# circuito_tesi.net
KiCad netlist of a schematic drawn in EAGLE
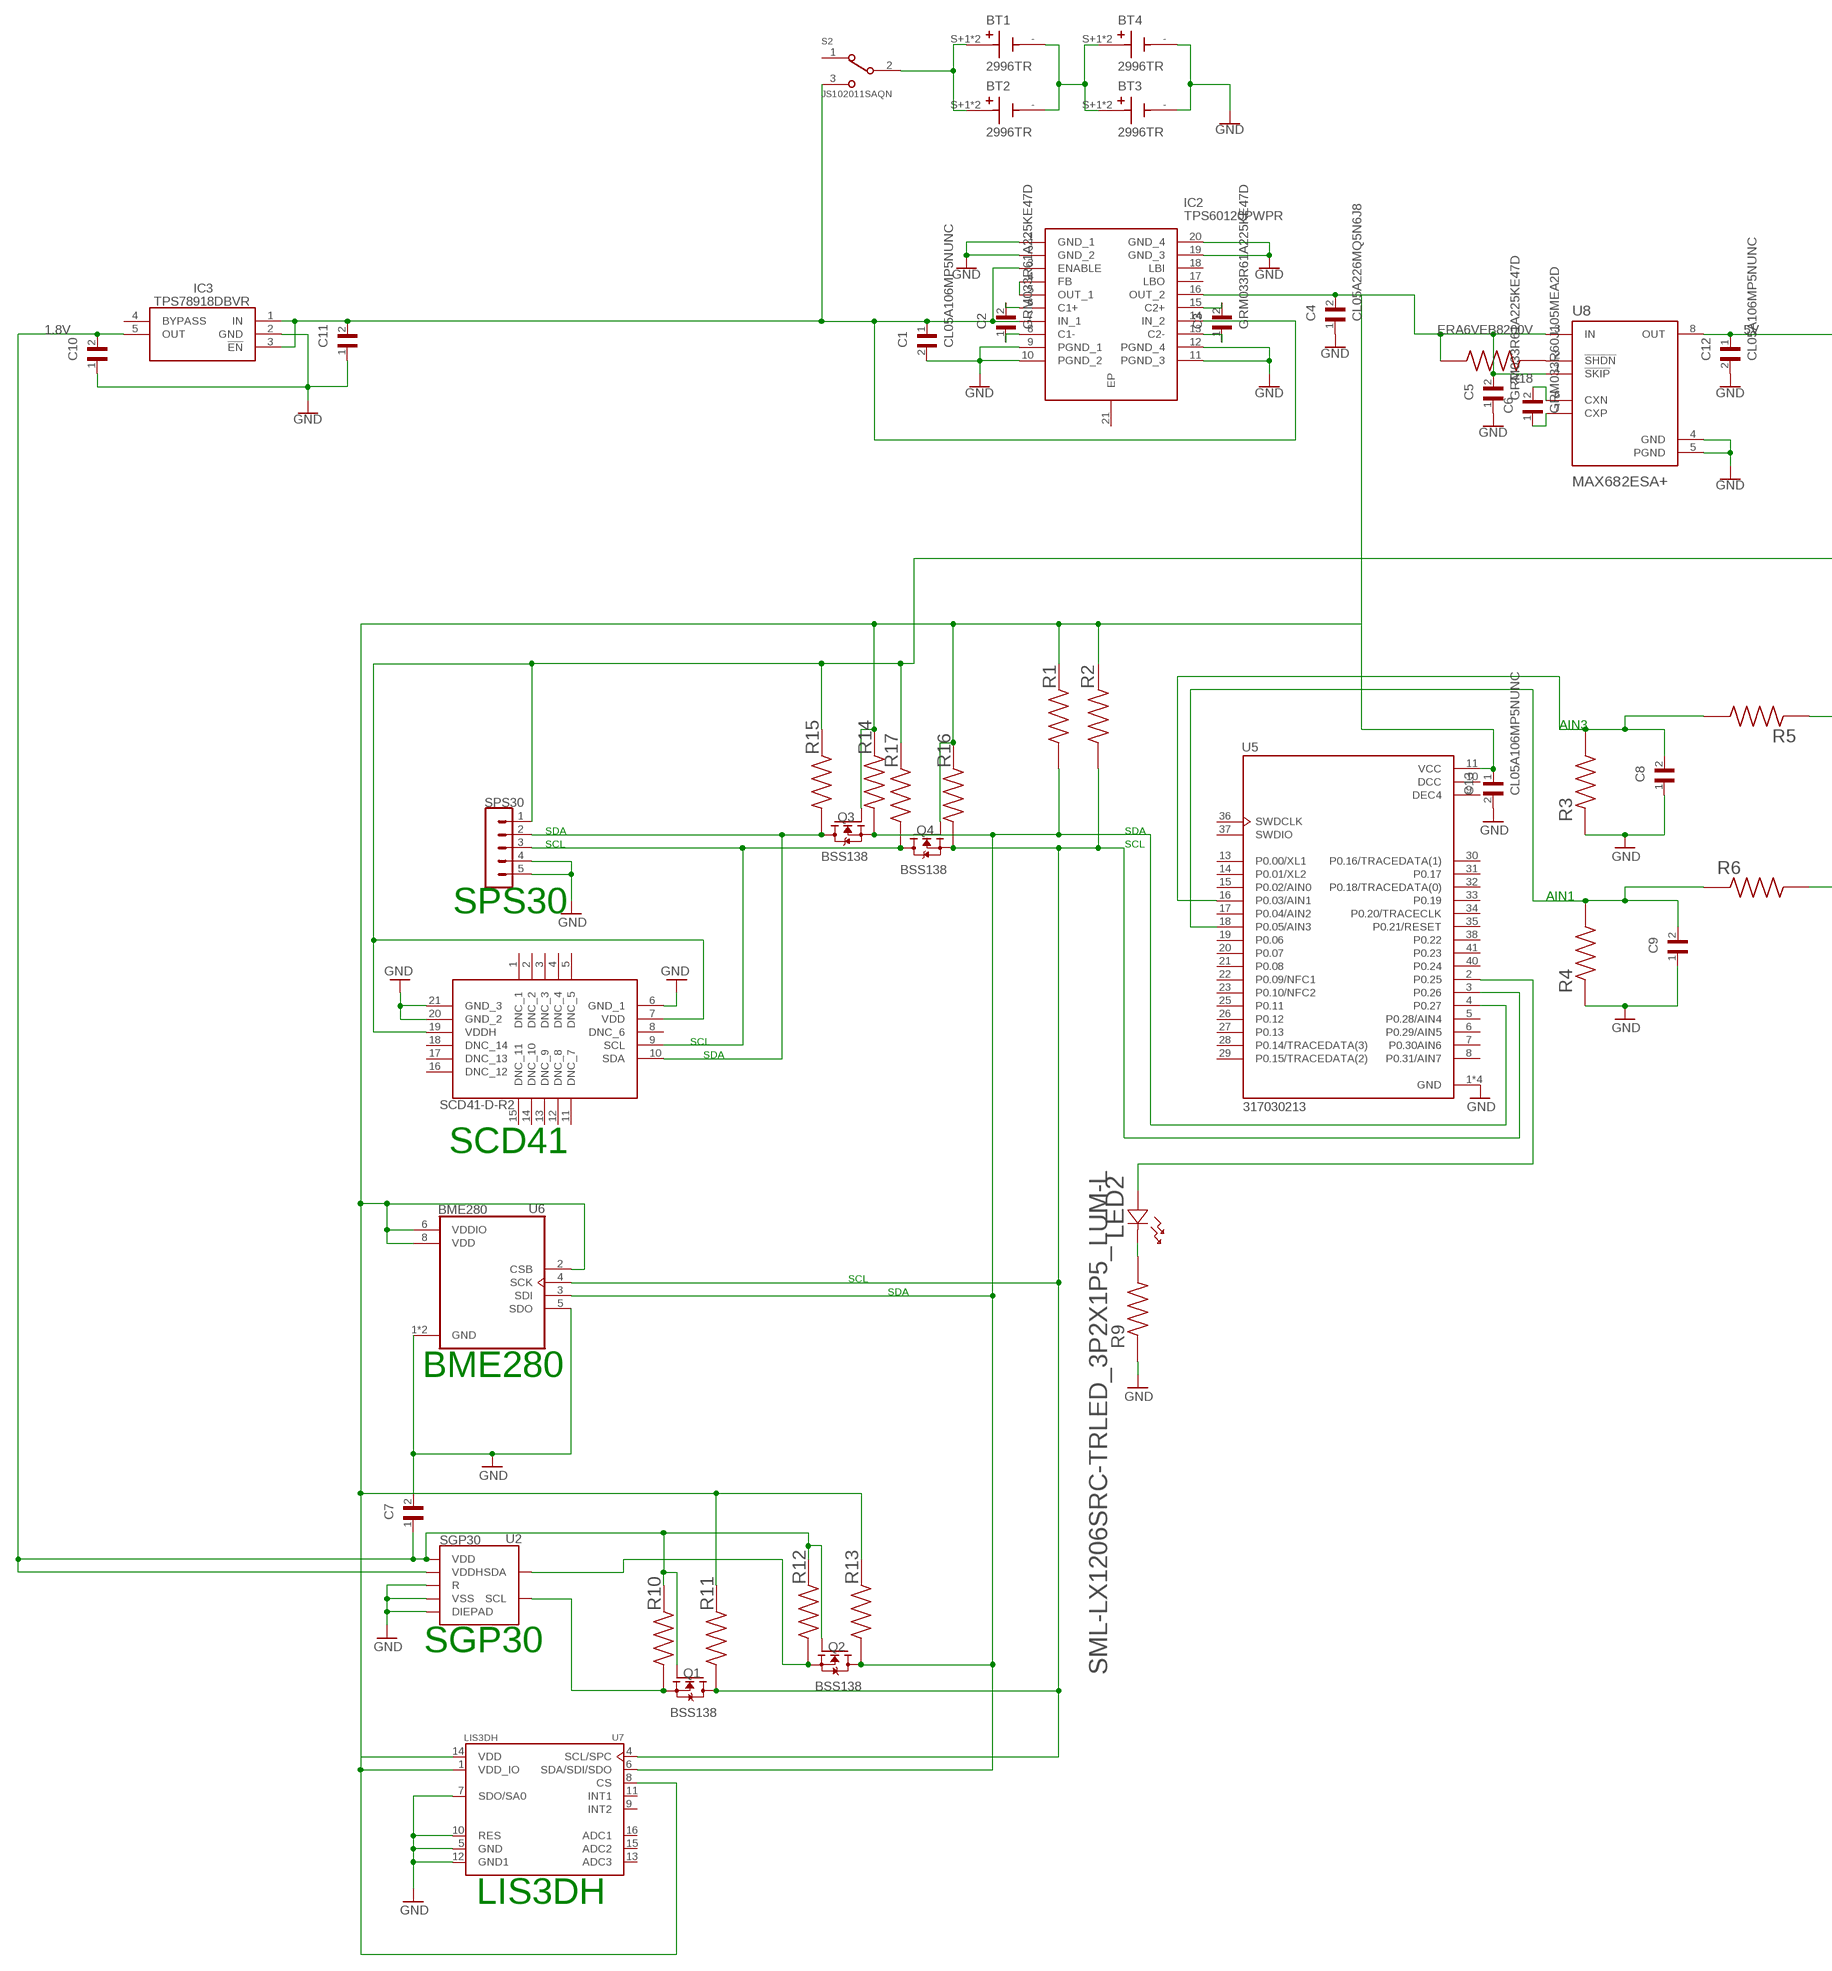
[diagram p0: schematic, sheet 1, part 1 of 2]
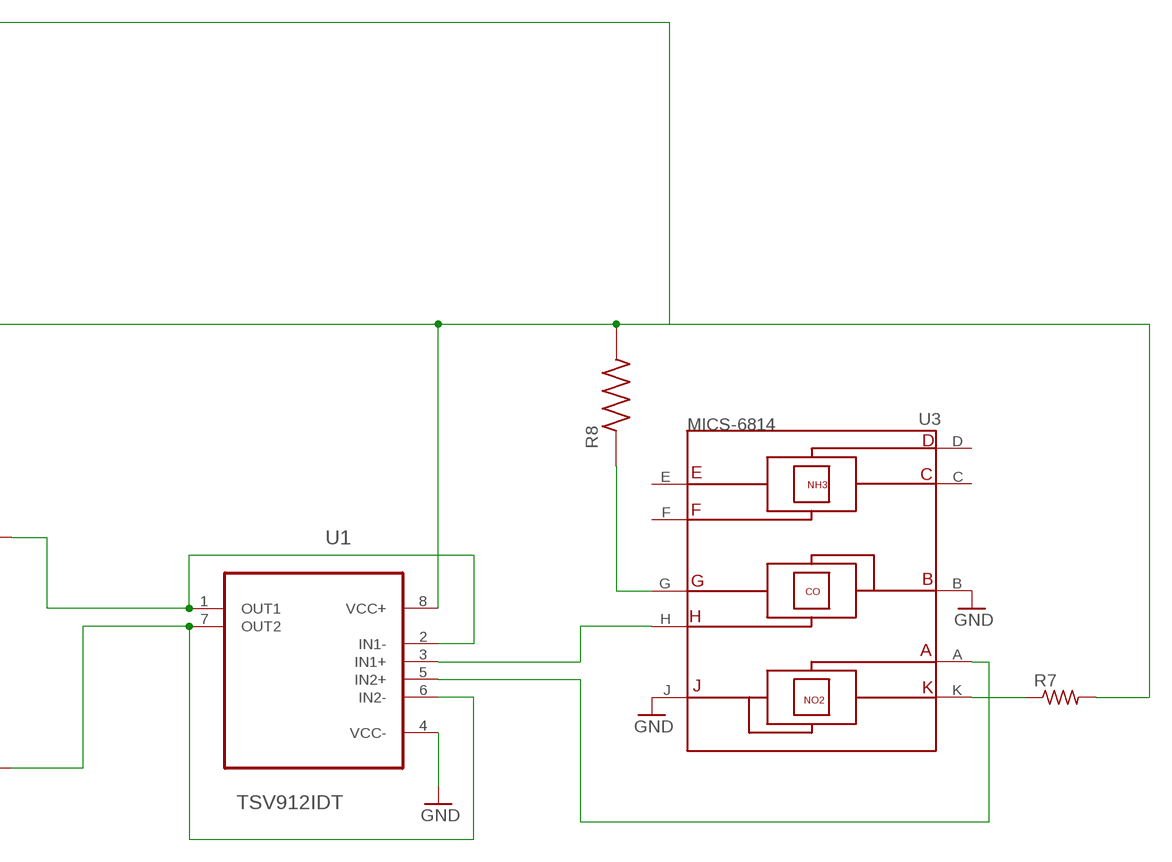
[diagram p1: schematic, sheet 1, part 2 of 2]

(export (version "E")
  (design (tool "Eeschema 10.0.6"))
  (components
    (comp (ref "BT1")
      (value "2996TR")
      (footprint "eagle-import:BAT_2996TR")
      (fields (field (name "DIGI-KEY_PART_NUMBER") "36-2996TR-ND") (field (name "MF") "Keystone Electronics"))
      (libsource (lib "eagle-import") (part "2996TR"))
    )
    (comp (ref "BT2")
      (value "2996TR")
      (footprint "eagle-import:BAT_2996TR")
      (fields (field (name "DIGI-KEY_PART_NUMBER") "36-2996TR-ND") (field (name "MF") "Keystone Electronics"))
      (libsource (lib "eagle-import") (part "2996TR"))
    )
    (comp (ref "BT3")
      (value "2996TR")
      (footprint "eagle-import:BAT_2996TR")
      (fields (field (name "DIGI-KEY_PART_NUMBER") "36-2996TR-ND") (field (name "MF") "Keystone Electronics"))
      (libsource (lib "eagle-import") (part "2996TR"))
    )
    (comp (ref "BT4")
      (value "2996TR")
      (footprint "eagle-import:BAT_2996TR")
      (fields (field (name "DIGI-KEY_PART_NUMBER") "36-2996TR-ND") (field (name "MF") "Keystone Electronics"))
      (libsource (lib "eagle-import") (part "2996TR"))
    )
    (comp (ref "C1")
      (value "CL05A106MP5NUNC")
      (footprint "eagle-import:CAPC1005X55N")
      (fields (field (name "DIGI-KEY_PART_NUMBER") "1276-1450-2-ND") (field (name "MF") "Samsung"))
      (libsource (lib "eagle-import") (part "CL05A106MP5NUNC"))
    )
    (comp (ref "C2")
      (value "GRM033R61A225KE47D")
      (footprint "eagle-import:CAPC0603X39N")
      (fields (field (name "DIGI-KEY_PART_NUMBER") "490-13227-2-ND") (field (name "MF") "Murata Electronics"))
      (libsource (lib "eagle-import") (part "GRM033R61A225KE47D"))
    )
    (comp (ref "C3")
      (value "GRM033R61A225KE47D")
      (footprint "eagle-import:CAPC0603X39N")
      (fields (field (name "DIGI-KEY_PART_NUMBER") "490-13227-2-ND") (field (name "MF") "Murata Electronics"))
      (libsource (lib "eagle-import") (part "GRM033R61A225KE47D"))
    )
    (comp (ref "C4")
      (value "CL05A226MQ5N6J8")
      (footprint "eagle-import:CAPC1005X55N")
      (fields
        (field (name "DIGI-KEY_PART_NUMBER") "1276-7090-2-ND")
        (field (name "MF") "Samsung Electro-Mechanics")
      )
      (libsource (lib "eagle-import") (part "CL05A226MQ5N6J8"))
    )
    (comp (ref "C5")
      (value "GRM033R61A225KE47D")
      (footprint "eagle-import:CAPC0603X39N")
      (fields (field (name "DIGI-KEY_PART_NUMBER") "490-13227-2-ND") (field (name "MF") "Murata Electronics"))
      (libsource (lib "eagle-import") (part "GRM033R61A225KE47D"))
    )
    (comp (ref "C6")
      (value "GRM033R60J105MEA2D")
      (footprint "eagle-import:CAPC0603X35N")
      (fields (field (name "DIGI-KEY_PART_NUMBER") "490-7229-2-ND") (field (name "MF") "Murata"))
      (libsource (lib "eagle-import") (part "GRM033R60J105MEA2D"))
    )
    (comp (ref "C7")
      (value "GRM033C80J104KE15D")
      (footprint "eagle-import:CAPC0603X33N")
      (fields (field (name "DIGI-KEY_PART_NUMBER") "490-10390-2-ND") (field (name "MF") "Murata Electronics"))
      (libsource (lib "eagle-import") (part "GRM033C80J104KE15D"))
    )
    (comp (ref "C8")
      (value "GRM033R60J103KA01D")
      (footprint "eagle-import:CAPC0603X33N")
      (fields (field (name "DIGI-KEY_PART_NUMBER") "490-5403-2-ND") (field (name "MF") "Murata"))
      (libsource (lib "eagle-import") (part "GRM033R60J103KA01D"))
    )
    (comp (ref "C9")
      (value "GRM033R60J103KA01D")
      (footprint "eagle-import:CAPC0603X33N")
      (fields (field (name "DIGI-KEY_PART_NUMBER") "490-5403-2-ND") (field (name "MF") "Murata"))
      (libsource (lib "eagle-import") (part "GRM033R60J103KA01D"))
    )
    (comp (ref "C10")
      (value "GRM033R60J105MEA2D")
      (footprint "eagle-import:CAPC0603X35N")
      (fields (field (name "DIGI-KEY_PART_NUMBER") "490-7229-2-ND") (field (name "MF") "Murata"))
      (libsource (lib "eagle-import") (part "GRM033R60J105MEA2D"))
    )
    (comp (ref "C11")
      (value "GRM033R60J105MEA2D")
      (footprint "eagle-import:CAPC0603X35N")
      (fields (field (name "DIGI-KEY_PART_NUMBER") "490-7229-2-ND") (field (name "MF") "Murata"))
      (libsource (lib "eagle-import") (part "GRM033R60J105MEA2D"))
    )
    (comp (ref "C12")
      (value "CL05A106MP5NUNC")
      (footprint "eagle-import:CAPC1005X55N")
      (fields (field (name "DIGI-KEY_PART_NUMBER") "1276-1450-2-ND") (field (name "MF") "Samsung"))
      (libsource (lib "eagle-import") (part "CL05A106MP5NUNC"))
    )
    (comp (ref "C13")
      (value "CL05A106MP5NUNC")
      (footprint "eagle-import:CAPC1005X55N")
      (fields (field (name "DIGI-KEY_PART_NUMBER") "1276-1450-2-ND") (field (name "MF") "Samsung"))
      (libsource (lib "eagle-import") (part "CL05A106MP5NUNC"))
    )
    (comp (ref "IC1")
      (value "SCD41-D-R2")
      (footprint "eagle-import:SCD41DR2")
      (fields (field (name "MOUSER_PART_NUMBER") "403-SCD41-D-R2"))
      (libsource (lib "eagle-import") (part "SCD41-D-R2"))
    )
    (comp (ref "IC2")
      (value "TPS60120PWPR")
      (footprint "eagle-import:SOP65P640X120-21N")
      (fields (field (name "MOUSER_PART_NUMBER") "595-TPS60120PWPR"))
      (libsource (lib "eagle-import") (part "TPS60120PWPR"))
    )
    (comp (ref "IC3")
      (value "TPS78918DBVR")
      (footprint "eagle-import:SOT95P280X145-5N")
      (fields (field (name "MOUSER_PART_NUMBER") "595-TPS78918DBVR"))
      (libsource (lib "eagle-import") (part "TPS78918DBVR"))
    )
    (comp (ref "LED2")
      (value "SML-LX1206SRC-TRLED_3P2X1P5_LUM-L")
      (footprint "eagle-import:LED_3P2X1P5_LUM-L")
      (fields
        (field (name "MANUFACTURER_PART_NUMBER") "SML-LX1206SRC-TR")
        (field (name "COPYRIGHT") "Copyright (C) 2022 Ultra Librarian. All rights reserved.")
      )
      (libsource (lib "eagle-import") (part "SML-LX1206SRC-TRLED_3P2X1P5_LUM-L"))
    )
    (comp (ref "Q1")
      (value "BSS138")
      (footprint "eagle-import:SOT95P240X111-3N")
      (fields (field (name "DIGI-KEY_PART_NUMBER") "BSS138TR-ND") (field (name "MF") "ON Semiconductor"))
      (libsource (lib "eagle-import") (part "BSS138"))
    )
    (comp (ref "Q2")
      (value "BSS138")
      (footprint "eagle-import:SOT95P240X111-3N")
      (fields (field (name "DIGI-KEY_PART_NUMBER") "BSS138TR-ND") (field (name "MF") "ON Semiconductor"))
      (libsource (lib "eagle-import") (part "BSS138"))
    )
    (comp (ref "Q3")
      (value "BSS138")
      (footprint "eagle-import:SOT95P240X111-3N")
      (fields (field (name "DIGI-KEY_PART_NUMBER") "BSS138TR-ND") (field (name "MF") "ON Semiconductor"))
      (libsource (lib "eagle-import") (part "BSS138"))
    )
    (comp (ref "Q4")
      (value "BSS138")
      (footprint "eagle-import:SOT95P240X111-3N")
      (fields (field (name "DIGI-KEY_PART_NUMBER") "BSS138TR-ND") (field (name "MF") "ON Semiconductor"))
      (libsource (lib "eagle-import") (part "BSS138"))
    )
    (comp (ref "R1")
      (value "RNCP0805FTD10K0")
      (footprint "eagle-import:RESC2012X60N")
      (fields
        (field (name "DIGI-KEY_PART_NUMBER") "RNCP0805FTD10K0TR-ND")
        (field (name "MF") "Stackpole Electronics Inc")
      )
      (libsource (lib "eagle-import") (part "RNCP0805FTD10K0"))
    )
    (comp (ref "R2")
      (value "RNCP0805FTD10K0")
      (footprint "eagle-import:RESC2012X60N")
      (fields
        (field (name "DIGI-KEY_PART_NUMBER") "RNCP0805FTD10K0TR-ND")
        (field (name "MF") "Stackpole Electronics Inc")
      )
      (libsource (lib "eagle-import") (part "RNCP0805FTD10K0"))
    )
    (comp (ref "R3")
      (value "RMCF0603FT10M0")
      (footprint "eagle-import:RESC1508X55N")
      (fields
        (field (name "DIGI-KEY_PART_NUMBER") "RMCF0603FT10M0TR-ND")
        (field (name "MF") "Stackpole Electronics Inc")
      )
      (libsource (lib "eagle-import") (part "RMCF0603FT10M0"))
    )
    (comp (ref "R4")
      (value "RMCF0603FT10M0")
      (footprint "eagle-import:RESC1508X55N")
      (fields
        (field (name "DIGI-KEY_PART_NUMBER") "RMCF0603FT10M0TR-ND")
        (field (name "MF") "Stackpole Electronics Inc")
      )
      (libsource (lib "eagle-import") (part "RMCF0603FT10M0"))
    )
    (comp (ref "R5")
      (value "RMCF0603FT5M10")
      (footprint "eagle-import:RESC1508X55N")
      (fields
        (field (name "DIGI-KEY_PART_NUMBER") "RMCF0603FT5M10TR-ND")
        (field (name "MF") "Stackpole Electronics Inc")
      )
      (libsource (lib "eagle-import") (part "RMCF0603FT5M10"))
    )
    (comp (ref "R6")
      (value "RMCF0603FT5M10")
      (footprint "eagle-import:RESC1508X55N")
      (fields
        (field (name "DIGI-KEY_PART_NUMBER") "RMCF0603FT5M10TR-ND")
        (field (name "MF") "Stackpole Electronics Inc")
      )
      (libsource (lib "eagle-import") (part "RMCF0603FT5M10"))
    )
    (comp (ref "R7")
      (value "RP73PF2A130RBTDF")
      (footprint "eagle-import:RESC2012X65N")
      (fields (field (name "MF") "TE Connectivity"))
      (libsource (lib "eagle-import") (part "RP73PF2A130RBTDF"))
    )
    (comp (ref "R8")
      (value "ERA6VEB8200V")
      (footprint "eagle-import:RES_ERA6VEB8200V")
      (fields (field (name "DIGI-KEY_PART_NUMBER") "10-ERA-6VEB8200VTR-ND") (field (name "MF") "Panasonic"))
      (libsource (lib "eagle-import") (part "ERA6VEB8200V"))
    )
    (comp (ref "R9")
      (value "RNCF0603DTE820R")
      (footprint "eagle-import:RESC1508X55N")
      (fields
        (field (name "DIGI-KEY_PART_NUMBER") "RNCF0603DTE820RTR-ND")
        (field (name "MF") "Stackpole Electronics Inc")
      )
      (libsource (lib "eagle-import") (part "RNCF0603DTE820R"))
    )
    (comp (ref "R10")
      (value "RNCP0805FTD10K0")
      (footprint "eagle-import:RESC2012X60N")
      (fields
        (field (name "DIGI-KEY_PART_NUMBER") "RNCP0805FTD10K0TR-ND")
        (field (name "MF") "Stackpole Electronics Inc")
      )
      (libsource (lib "eagle-import") (part "RNCP0805FTD10K0"))
    )
    (comp (ref "R11")
      (value "RNCP0805FTD10K0")
      (footprint "eagle-import:RESC2012X60N")
      (fields
        (field (name "DIGI-KEY_PART_NUMBER") "RNCP0805FTD10K0TR-ND")
        (field (name "MF") "Stackpole Electronics Inc")
      )
      (libsource (lib "eagle-import") (part "RNCP0805FTD10K0"))
    )
    (comp (ref "R12")
      (value "RNCP0805FTD10K0")
      (footprint "eagle-import:RESC2012X60N")
      (fields
        (field (name "DIGI-KEY_PART_NUMBER") "RNCP0805FTD10K0TR-ND")
        (field (name "MF") "Stackpole Electronics Inc")
      )
      (libsource (lib "eagle-import") (part "RNCP0805FTD10K0"))
    )
    (comp (ref "R13")
      (value "RNCP0805FTD10K0")
      (footprint "eagle-import:RESC2012X60N")
      (fields
        (field (name "DIGI-KEY_PART_NUMBER") "RNCP0805FTD10K0TR-ND")
        (field (name "MF") "Stackpole Electronics Inc")
      )
      (libsource (lib "eagle-import") (part "RNCP0805FTD10K0"))
    )
    (comp (ref "R14")
      (value "RNCP0805FTD10K0")
      (footprint "eagle-import:RESC2012X60N")
      (fields
        (field (name "DIGI-KEY_PART_NUMBER") "RNCP0805FTD10K0TR-ND")
        (field (name "MF") "Stackpole Electronics Inc")
      )
      (libsource (lib "eagle-import") (part "RNCP0805FTD10K0"))
    )
    (comp (ref "R15")
      (value "RNCP0805FTD10K0")
      (footprint "eagle-import:RESC2012X60N")
      (fields
        (field (name "DIGI-KEY_PART_NUMBER") "RNCP0805FTD10K0TR-ND")
        (field (name "MF") "Stackpole Electronics Inc")
      )
      (libsource (lib "eagle-import") (part "RNCP0805FTD10K0"))
    )
    (comp (ref "R16")
      (value "RNCP0805FTD10K0")
      (footprint "eagle-import:RESC2012X60N")
      (fields
        (field (name "DIGI-KEY_PART_NUMBER") "RNCP0805FTD10K0TR-ND")
        (field (name "MF") "Stackpole Electronics Inc")
      )
      (libsource (lib "eagle-import") (part "RNCP0805FTD10K0"))
    )
    (comp (ref "R17")
      (value "RNCP0805FTD10K0")
      (footprint "eagle-import:RESC2012X60N")
      (fields
        (field (name "DIGI-KEY_PART_NUMBER") "RNCP0805FTD10K0TR-ND")
        (field (name "MF") "Stackpole Electronics Inc")
      )
      (libsource (lib "eagle-import") (part "RNCP0805FTD10K0"))
    )
    (comp (ref "R18")
      (value "ERA6VEB8200V")
      (footprint "eagle-import:RES_ERA6VEB8200V")
      (fields (field (name "DIGI-KEY_PART_NUMBER") "10-ERA-6VEB8200VTR-ND") (field (name "MF") "Panasonic"))
      (libsource (lib "eagle-import") (part "ERA6VEB8200V"))
    )
    (comp (ref "S2")
      (value "JS102011SAQN")
      (footprint "eagle-import:SW_JS102011SAQN")
      (fields (field (name "DIGI-KEY_PART_NUMBER") "401-1999-2-ND") (field (name "MF") "C&K"))
      (libsource (lib "eagle-import") (part "JS102011SAQN"))
    )
    (comp (ref "SPS30")
      (value "MA05-1")
      (footprint "eagle-import:MA05-1")
      (libsource (lib "eagle-import") (part "MA05-1"))
    )
    (comp (ref "U1")
      (value "TSV912IDT")
      (footprint "eagle-import:SOIC127P600X175-8N")
      (fields (field (name "MF") "STMicroelectronics"))
      (libsource (lib "eagle-import") (part "TSV912IDT"))
    )
    (comp (ref "U2")
      (value "SGP30")
      (footprint "eagle-import:SGP30")
      (fields (field (name "MF") "Sensirion AG"))
      (libsource (lib "eagle-import") (part "SGP30"))
    )
    (comp (ref "U3")
      (value "MICS-6814")
      (footprint "eagle-import:SENSOR_MICS-6814")
      (fields (field (name "MF") "MikroElektronika"))
      (libsource (lib "eagle-import") (part "MICS-6814"))
    )
    (comp (ref "U5")
      (value "317030213")
      (footprint "eagle-import:XCVR_317030213")
      (fields (field (name "DIGI-KEY_PART_NUMBER") "1597-1434-ND") (field (name "MF") "Seeed Technology"))
      (libsource (lib "eagle-import") (part "317030213"))
    )
    (comp (ref "U6")
      (value "BME280")
      (footprint "eagle-import:PSON65P250X250X100-8N")
      (fields (field (name "MF") "Bosch"))
      (libsource (lib "eagle-import") (part "BME280"))
    )
    (comp (ref "U7")
      (value "LIS3DH")
      (footprint "eagle-import:PQFN50P300X300X100-16N")
      (fields (field (name "DIGI-KEY_PART_NUMBER") "497-10610-ND") (field (name "MF") "STMicroelectronics"))
      (libsource (lib "eagle-import") (part "LIS3DH"))
    )
    (comp (ref "U8")
      (value "MAX682ESA+")
      (footprint "eagle-import:SOIC127P600X175-8N")
      (fields (field (name "DIGI-KEY_PART_NUMBER") "MAX682ESA+-ND") (field (name "MF") "Maxim Integrated"))
      (libsource (lib "eagle-import") (part "MAX682ESA+"))
    )
  )
  (nets
    (net (code "1") (name "/1.8V") (class "Default")
      (node (ref "C10") (pin "2") (pinfunction "2_2") (pintype "passive"))
      (node (ref "C7") (pin "1") (pinfunction "1_1") (pintype "passive"))
      (node (ref "IC3") (pin "5") (pinfunction "OUT_5") (pintype "bidirectional"))
      (node (ref "Q1") (pin "1") (pinfunction "G_1") (pintype "passive"))
      (node (ref "Q2") (pin "1") (pinfunction "G_1") (pintype "passive"))
      (node (ref "R10") (pin "2") (pinfunction "2_2") (pintype "passive"))
      (node (ref "R12") (pin "2") (pinfunction "2_2") (pintype "passive"))
      (node (ref "U2") (pin "1") (pinfunction "VDD_1") (pintype "bidirectional"))
      (node (ref "U2") (pin "5") (pinfunction "VDDH_5") (pintype "bidirectional"))
    )
    (net (code "2") (name "/5V") (class "Default")
      (node (ref "C12") (pin "1") (pinfunction "1_1") (pintype "passive"))
      (node (ref "IC1") (pin "19") (pinfunction "VDDH_19") (pintype "bidirectional"))
      (node (ref "IC1") (pin "7") (pinfunction "VDD_7") (pintype "bidirectional"))
      (node (ref "R15") (pin "2") (pinfunction "2_2") (pintype "passive"))
      (node (ref "R17") (pin "2") (pinfunction "2_2") (pintype "passive"))
      (node (ref "R7") (pin "2") (pinfunction "2_2") (pintype "passive"))
      (node (ref "R8") (pin "2") (pinfunction "2_2") (pintype "passive"))
      (node (ref "SPS30") (pin "1") (pinfunction "1_1") (pintype "passive"))
      (node (ref "U1") (pin "8") (pinfunction "VCC+_8") (pintype "power_in"))
      (node (ref "U8") (pin "8") (pinfunction "OUT_8") (pintype "output"))
    )
    (net (code "3") (name "/DCC") (class "Default")
      (node (ref "U5") (pin "10") (pinfunction "DCC_10") (pintype "power_in"))
    )
    (net (code "4") (name "/DEC4") (class "Default")
      (node (ref "U5") (pin "9") (pinfunction "DEC4_9") (pintype "power_in"))
    )
    (net (code "5") (name "GND") (class "Default")
      (node (ref "BT3") (pin "-") (pinfunction "-_-") (pintype "passive"))
      (node (ref "BT4") (pin "-") (pinfunction "-_-") (pintype "passive"))
      (node (ref "C1") (pin "2") (pinfunction "2_2") (pintype "passive"))
      (node (ref "C10") (pin "1") (pinfunction "1_1") (pintype "passive"))
      (node (ref "C11") (pin "1") (pinfunction "1_1") (pintype "passive"))
      (node (ref "C12") (pin "2") (pinfunction "2_2") (pintype "passive"))
      (node (ref "C13") (pin "2") (pinfunction "2_2") (pintype "passive"))
      (node (ref "C4") (pin "1") (pinfunction "1_1") (pintype "passive"))
      (node (ref "C5") (pin "1") (pinfunction "1_1") (pintype "passive"))
      (node (ref "C7") (pin "2") (pinfunction "2_2") (pintype "passive"))
      (node (ref "C8") (pin "1") (pinfunction "1_1") (pintype "passive"))
      (node (ref "C9") (pin "1") (pinfunction "1_1") (pintype "passive"))
      (node (ref "IC1") (pin "20") (pinfunction "GND_2_20") (pintype "bidirectional"))
      (node (ref "IC1") (pin "21") (pinfunction "GND_3_21") (pintype "bidirectional"))
      (node (ref "IC1") (pin "6") (pinfunction "GND_1_6") (pintype "bidirectional"))
      (node (ref "IC2") (pin "1") (pinfunction "GND_1_1") (pintype "bidirectional"))
      (node (ref "IC2") (pin "10") (pinfunction "PGND_2_10") (pintype "bidirectional"))
      (node (ref "IC2") (pin "11") (pinfunction "PGND_3_11") (pintype "bidirectional"))
      (node (ref "IC2") (pin "12") (pinfunction "PGND_4_12") (pintype "bidirectional"))
      (node (ref "IC2") (pin "19") (pinfunction "GND_3_19") (pintype "bidirectional"))
      (node (ref "IC2") (pin "2") (pinfunction "GND_2_2") (pintype "bidirectional"))
      (node (ref "IC2") (pin "20") (pinfunction "GND_4_20") (pintype "bidirectional"))
      (node (ref "IC2") (pin "9") (pinfunction "PGND_1_9") (pintype "bidirectional"))
      (node (ref "IC3") (pin "2") (pinfunction "GND_2") (pintype "bidirectional"))
      (node (ref "R3") (pin "1") (pinfunction "1_1") (pintype "passive"))
      (node (ref "R4") (pin "1") (pinfunction "1_1") (pintype "passive"))
      (node (ref "R9") (pin "1") (pinfunction "1_1") (pintype "passive"))
      (node (ref "SPS30") (pin "4") (pinfunction "4_4") (pintype "passive"))
      (node (ref "SPS30") (pin "5") (pinfunction "5_5") (pintype "passive"))
      (node (ref "U1") (pin "4") (pinfunction "VCC-_4") (pintype "power_in"))
      (node (ref "U2") (pin "2") (pinfunction "VSS_2") (pintype "bidirectional"))
      (node (ref "U2") (pin "4") (pinfunction "R_4") (pintype "bidirectional"))
      (node (ref "U2") (pin "DIEPAD") (pinfunction "DIEPAD_DIEPAD") (pintype "bidirectional"))
      (node (ref "U3") (pin "B") (pinfunction "RH1/RS1_RED_B") (pintype "passive"))
      (node (ref "U3") (pin "J") (pinfunction "RH1/RS1_OX_J") (pintype "passive"))
      (node (ref "U5") (pin "1") (pinfunction "GND_1") (pintype "power_in"))
      (node (ref "U5") (pin "12") (pinfunction "GND_12") (pintype "power_in"))
      (node (ref "U5") (pin "24") (pinfunction "GND_24") (pintype "power_in"))
      (node (ref "U5") (pin "39") (pinfunction "GND_39") (pintype "power_in"))
      (node (ref "U6") (pin "1") (pinfunction "GND_1") (pintype "power_in"))
      (node (ref "U6") (pin "5") (pinfunction "SDO_5") (pintype "bidirectional"))
      (node (ref "U6") (pin "7") (pinfunction "GND_7") (pintype "power_in"))
      (node (ref "U7") (pin "10") (pinfunction "RES_10") (pintype "power_in"))
      (node (ref "U7") (pin "12") (pinfunction "GND1_12") (pintype "power_in"))
      (node (ref "U7") (pin "5") (pinfunction "GND_5") (pintype "power_in"))
      (node (ref "U7") (pin "7") (pinfunction "SDO/SA0_7") (pintype "output"))
      (node (ref "U8") (pin "4") (pinfunction "GND_4") (pintype "power_in"))
      (node (ref "U8") (pin "5") (pinfunction "PGND_5") (pintype "power_in"))
    )
    (net (code "6") (name "Net-(BT1-+-PadS+1)") (class "Default")
      (node (ref "BT1") (pin "S+1") (pinfunction "+_S+1") (pintype "passive"))
      (node (ref "BT1") (pin "S+2") (pinfunction "+_S+2") (pintype "passive"))
      (node (ref "BT2") (pin "S+1") (pinfunction "+_S+1") (pintype "passive"))
      (node (ref "BT2") (pin "S+2") (pinfunction "+_S+2") (pintype "passive"))
      (node (ref "S2") (pin "2") (pinfunction "2_2") (pintype "passive"))
    )
    (net (code "7") (name "Net-(BT1-Pad-)") (class "Default")
      (node (ref "BT1") (pin "-") (pinfunction "-_-") (pintype "passive"))
      (node (ref "BT2") (pin "-") (pinfunction "-_-") (pintype "passive"))
      (node (ref "BT3") (pin "S+1") (pinfunction "+_S+1") (pintype "passive"))
      (node (ref "BT3") (pin "S+2") (pinfunction "+_S+2") (pintype "passive"))
      (node (ref "BT4") (pin "S+1") (pinfunction "+_S+1") (pintype "passive"))
      (node (ref "BT4") (pin "S+2") (pinfunction "+_S+2") (pintype "passive"))
    )
    (net (code "8") (name "Net-(IC1-SCL)") (class "Default")
      (node (ref "IC1") (pin "9") (pinfunction "SCL_9") (pintype "bidirectional"))
      (node (ref "Q4") (pin "3") (pinfunction "D_3") (pintype "passive"))
      (node (ref "R17") (pin "1") (pinfunction "1_1") (pintype "passive"))
      (node (ref "SPS30") (pin "3") (pinfunction "3_3") (pintype "passive"))
    )
    (net (code "9") (name "Net-(IC1-SDA)") (class "Default")
      (node (ref "IC1") (pin "10") (pinfunction "SDA_10") (pintype "bidirectional"))
      (node (ref "Q3") (pin "3") (pinfunction "D_3") (pintype "passive"))
      (node (ref "R15") (pin "1") (pinfunction "1_1") (pintype "passive"))
      (node (ref "SPS30") (pin "2") (pinfunction "2_2") (pintype "passive"))
    )
    (net (code "10") (name "Net-(IC2-C1+)") (class "Default")
      (node (ref "C2") (pin "2") (pinfunction "2_2") (pintype "passive"))
      (node (ref "IC2") (pin "6") (pinfunction "C1+_6") (pintype "bidirectional"))
    )
    (net (code "11") (name "Net-(IC2-C1-)") (class "Default")
      (node (ref "C2") (pin "1") (pinfunction "1_1") (pintype "passive"))
      (node (ref "IC2") (pin "8") (pinfunction "C1-_8") (pintype "bidirectional"))
    )
    (net (code "12") (name "Net-(IC2-C2+)") (class "Default")
      (node (ref "C3") (pin "2") (pinfunction "2_2") (pintype "passive"))
      (node (ref "IC2") (pin "15") (pinfunction "C2+_15") (pintype "bidirectional"))
    )
    (net (code "13") (name "Net-(IC2-C2-)") (class "Default")
      (node (ref "C3") (pin "1") (pinfunction "1_1") (pintype "passive"))
      (node (ref "IC2") (pin "13") (pinfunction "C2-_13") (pintype "bidirectional"))
    )
    (net (code "14") (name "Net-(IC2-ENABLE)") (class "Default")
      (node (ref "C1") (pin "1") (pinfunction "1_1") (pintype "passive"))
      (node (ref "C11") (pin "2") (pinfunction "2_2") (pintype "passive"))
      (node (ref "IC2") (pin "14") (pinfunction "IN_2_14") (pintype "bidirectional"))
      (node (ref "IC2") (pin "3") (pinfunction "ENABLE_3") (pintype "bidirectional"))
      (node (ref "IC2") (pin "7") (pinfunction "IN_1_7") (pintype "bidirectional"))
      (node (ref "IC3") (pin "1") (pinfunction "IN_1") (pintype "bidirectional"))
      (node (ref "IC3") (pin "3") (pinfunction "~{EN}_3") (pintype "bidirectional"))
      (node (ref "S2") (pin "3") (pinfunction "3_3") (pintype "passive"))
    )
    (net (code "15") (name "Net-(IC2-FB)") (class "Default")
      (node (ref "IC2") (pin "4") (pinfunction "FB_4") (pintype "bidirectional"))
      (node (ref "IC2") (pin "5") (pinfunction "OUT_1_5") (pintype "bidirectional"))
    )
    (net (code "16") (name "Net-(IC2-OUT_2)") (class "Default")
      (node (ref "C13") (pin "1") (pinfunction "1_1") (pintype "passive"))
      (node (ref "C4") (pin "2") (pinfunction "2_2") (pintype "passive"))
      (node (ref "C5") (pin "2") (pinfunction "2_2") (pintype "passive"))
      (node (ref "IC2") (pin "16") (pinfunction "OUT_2_16") (pintype "bidirectional"))
      (node (ref "Q3") (pin "1") (pinfunction "G_1") (pintype "passive"))
      (node (ref "Q4") (pin "1") (pinfunction "G_1") (pintype "passive"))
      (node (ref "R1") (pin "2") (pinfunction "2_2") (pintype "passive"))
      (node (ref "R11") (pin "2") (pinfunction "2_2") (pintype "passive"))
      (node (ref "R13") (pin "2") (pinfunction "2_2") (pintype "passive"))
      (node (ref "R14") (pin "2") (pinfunction "2_2") (pintype "passive"))
      (node (ref "R16") (pin "2") (pinfunction "2_2") (pintype "passive"))
      (node (ref "R18") (pin "2") (pinfunction "2_2") (pintype "passive"))
      (node (ref "R2") (pin "2") (pinfunction "2_2") (pintype "passive"))
      (node (ref "U5") (pin "11") (pinfunction "VCC_11") (pintype "power_in"))
      (node (ref "U6") (pin "2") (pinfunction "CSB_2") (pintype "input"))
      (node (ref "U6") (pin "6") (pinfunction "VDDIO_6") (pintype "power_in"))
      (node (ref "U6") (pin "8") (pinfunction "VDD_8") (pintype "power_in"))
      (node (ref "U7") (pin "1") (pinfunction "VDD_IO_1") (pintype "power_in"))
      (node (ref "U7") (pin "14") (pinfunction "VDD_14") (pintype "power_in"))
      (node (ref "U7") (pin "8") (pinfunction "CS_8") (pintype "input"))
      (node (ref "U8") (pin "1") (pinfunction "~{SKIP}_1") (pintype "input"))
      (node (ref "U8") (pin "3") (pinfunction "IN_3") (pintype "input"))
    )
    (net (code "17") (name "Net-(LED2-ANODE)") (class "Default")
      (node (ref "LED2") (pin "1") (pinfunction "ANODE_1") (pintype "passive"))
      (node (ref "R9") (pin "2") (pinfunction "2_2") (pintype "passive"))
    )
    (net (code "18") (name "Net-(LED2-CATHODE)") (class "Default")
      (node (ref "LED2") (pin "2") (pinfunction "CATHODE_2") (pintype "passive"))
      (node (ref "U5") (pin "2") (pinfunction "P0.25_2") (pintype "bidirectional"))
    )
    (net (code "19") (name "Net-(Q1-D)") (class "Default")
      (node (ref "Q1") (pin "3") (pinfunction "D_3") (pintype "passive"))
      (node (ref "Q4") (pin "2") (pinfunction "S_2") (pintype "passive"))
      (node (ref "R11") (pin "1") (pinfunction "1_1") (pintype "passive"))
      (node (ref "R16") (pin "1") (pinfunction "1_1") (pintype "passive"))
      (node (ref "R2") (pin "1") (pinfunction "1_1") (pintype "passive"))
      (node (ref "U5") (pin "3") (pinfunction "P0.26_3") (pintype "bidirectional"))
      (node (ref "U6") (pin "4") (pinfunction "SCK_4") (pintype "input"))
      (node (ref "U7") (pin "4") (pinfunction "SCL/SPC_4") (pintype "input"))
    )
    (net (code "20") (name "Net-(Q1-S)") (class "Default")
      (node (ref "Q1") (pin "2") (pinfunction "S_2") (pintype "passive"))
      (node (ref "R10") (pin "1") (pinfunction "1_1") (pintype "passive"))
      (node (ref "U2") (pin "6") (pinfunction "SCL_6") (pintype "bidirectional"))
    )
    (net (code "21") (name "Net-(Q2-D)") (class "Default")
      (node (ref "Q2") (pin "3") (pinfunction "D_3") (pintype "passive"))
      (node (ref "Q3") (pin "2") (pinfunction "S_2") (pintype "passive"))
      (node (ref "R1") (pin "1") (pinfunction "1_1") (pintype "passive"))
      (node (ref "R13") (pin "1") (pinfunction "1_1") (pintype "passive"))
      (node (ref "R14") (pin "1") (pinfunction "1_1") (pintype "passive"))
      (node (ref "U5") (pin "4") (pinfunction "P0.27_4") (pintype "bidirectional"))
      (node (ref "U6") (pin "3") (pinfunction "SDI_3") (pintype "bidirectional"))
      (node (ref "U7") (pin "6") (pinfunction "SDA/SDI/SDO_6") (pintype "input"))
    )
    (net (code "22") (name "Net-(Q2-S)") (class "Default")
      (node (ref "Q2") (pin "2") (pinfunction "S_2") (pintype "passive"))
      (node (ref "R12") (pin "1") (pinfunction "1_1") (pintype "passive"))
      (node (ref "U2") (pin "3") (pinfunction "SDA_3") (pintype "bidirectional"))
    )
    (net (code "23") (name "Net-(U1-IN1+)") (class "Default")
      (node (ref "U1") (pin "3") (pinfunction "IN1+_3") (pintype "input"))
      (node (ref "U3") (pin "H") (pinfunction "RS2_RED_H") (pintype "passive"))
    )
    (net (code "24") (name "Net-(U1-IN1-)") (class "Default")
      (node (ref "R5") (pin "1") (pinfunction "1_1") (pintype "passive"))
      (node (ref "U1") (pin "1") (pinfunction "OUT1_1") (pintype "output"))
      (node (ref "U1") (pin "2") (pinfunction "IN1-_2") (pintype "input"))
    )
    (net (code "25") (name "Net-(U1-IN2+)") (class "Default")
      (node (ref "U1") (pin "5") (pinfunction "IN2+_5") (pintype "input"))
      (node (ref "U3") (pin "A") (pinfunction "RS2_A") (pintype "passive"))
    )
    (net (code "26") (name "Net-(U1-IN2-)") (class "Default")
      (node (ref "R6") (pin "2") (pinfunction "2_2") (pintype "passive"))
      (node (ref "U1") (pin "6") (pinfunction "IN2-_6") (pintype "input"))
      (node (ref "U1") (pin "7") (pinfunction "OUT2_7") (pintype "output"))
    )
    (net (code "27") (name "Net-(U3-RH2_OX)") (class "Default")
      (node (ref "R7") (pin "1") (pinfunction "1_1") (pintype "passive"))
      (node (ref "U3") (pin "K") (pinfunction "RH2_OX_K") (pintype "passive"))
    )
    (net (code "28") (name "Net-(U3-RH2_RED)") (class "Default")
      (node (ref "R8") (pin "1") (pinfunction "1_1") (pintype "passive"))
      (node (ref "U3") (pin "G") (pinfunction "RH2_RED_G") (pintype "passive"))
    )
    (net (code "29") (name "Net-(U5-P0.03{slash}AIN1)") (class "Default")
      (node (ref "C8") (pin "2") (pinfunction "2_2") (pintype "passive"))
      (node (ref "R3") (pin "2") (pinfunction "2_2") (pintype "passive"))
      (node (ref "R5") (pin "2") (pinfunction "2_2") (pintype "passive"))
      (node (ref "U5") (pin "16") (pinfunction "P0.03/AIN1_16") (pintype "bidirectional"))
    )
    (net (code "30") (name "Net-(U5-P0.05{slash}AIN3)") (class "Default")
      (node (ref "C9") (pin "2") (pinfunction "2_2") (pintype "passive"))
      (node (ref "R4") (pin "2") (pinfunction "2_2") (pintype "passive"))
      (node (ref "R6") (pin "1") (pinfunction "1_1") (pintype "passive"))
      (node (ref "U5") (pin "18") (pinfunction "P0.05/AIN3_18") (pintype "bidirectional"))
    )
    (net (code "31") (name "Net-(U8-CXN)") (class "Default")
      (node (ref "C6") (pin "2") (pinfunction "2_2") (pintype "passive"))
      (node (ref "U8") (pin "6") (pinfunction "CXN_6") (pintype "passive"))
    )
    (net (code "32") (name "Net-(U8-CXP)") (class "Default")
      (node (ref "C6") (pin "1") (pinfunction "1_1") (pintype "passive"))
      (node (ref "U8") (pin "7") (pinfunction "CXP_7") (pintype "passive"))
    )
    (net (code "33") (name "Net-(U8-~{SHDN})") (class "Default")
      (node (ref "R18") (pin "1") (pinfunction "1_1") (pintype "passive"))
      (node (ref "U8") (pin "2") (pinfunction "~{SHDN}_2") (pintype "input"))
    )
    (net (code "34") (name "unconnected-(IC1-DNC_1-Pad1)") (class "Default")
      (node (ref "IC1") (pin "1") (pinfunction "DNC_1_1") (pintype "bidirectional"))
    )
    (net (code "35") (name "unconnected-(IC1-DNC_2-Pad2)") (class "Default")
      (node (ref "IC1") (pin "2") (pinfunction "DNC_2_2") (pintype "bidirectional"))
    )
    (net (code "36") (name "unconnected-(IC1-DNC_3-Pad3)") (class "Default")
      (node (ref "IC1") (pin "3") (pinfunction "DNC_3_3") (pintype "bidirectional"))
    )
    (net (code "37") (name "unconnected-(IC1-DNC_4-Pad4)") (class "Default")
      (node (ref "IC1") (pin "4") (pinfunction "DNC_4_4") (pintype "bidirectional"))
    )
    (net (code "38") (name "unconnected-(IC1-DNC_5-Pad5)") (class "Default")
      (node (ref "IC1") (pin "5") (pinfunction "DNC_5_5") (pintype "bidirectional"))
    )
    (net (code "39") (name "unconnected-(IC1-DNC_6-Pad8)") (class "Default")
      (node (ref "IC1") (pin "8") (pinfunction "DNC_6_8") (pintype "bidirectional"))
    )
    (net (code "40") (name "unconnected-(IC1-DNC_7-Pad11)") (class "Default")
      (node (ref "IC1") (pin "11") (pinfunction "DNC_7_11") (pintype "bidirectional"))
    )
    (net (code "41") (name "unconnected-(IC1-DNC_8-Pad12)") (class "Default")
      (node (ref "IC1") (pin "12") (pinfunction "DNC_8_12") (pintype "bidirectional"))
    )
    (net (code "42") (name "unconnected-(IC1-DNC_9-Pad13)") (class "Default")
      (node (ref "IC1") (pin "13") (pinfunction "DNC_9_13") (pintype "bidirectional"))
    )
    (net (code "43") (name "unconnected-(IC1-DNC_10-Pad14)") (class "Default")
      (node (ref "IC1") (pin "14") (pinfunction "DNC_10_14") (pintype "bidirectional"))
    )
    (net (code "44") (name "unconnected-(IC1-DNC_11-Pad15)") (class "Default")
      (node (ref "IC1") (pin "15") (pinfunction "DNC_11_15") (pintype "bidirectional"))
    )
    (net (code "45") (name "unconnected-(IC1-DNC_12-Pad16)") (class "Default")
      (node (ref "IC1") (pin "16") (pinfunction "DNC_12_16") (pintype "bidirectional"))
    )
    (net (code "46") (name "unconnected-(IC1-DNC_13-Pad17)") (class "Default")
      (node (ref "IC1") (pin "17") (pinfunction "DNC_13_17") (pintype "bidirectional"))
    )
    (net (code "47") (name "unconnected-(IC1-DNC_14-Pad18)") (class "Default")
      (node (ref "IC1") (pin "18") (pinfunction "DNC_14_18") (pintype "bidirectional"))
    )
    (net (code "48") (name "unconnected-(IC2-EP-Pad21)") (class "Default")
      (node (ref "IC2") (pin "21") (pinfunction "EP_21") (pintype "bidirectional"))
    )
    (net (code "49") (name "unconnected-(IC2-LBI-Pad18)") (class "Default")
      (node (ref "IC2") (pin "18") (pinfunction "LBI_18") (pintype "bidirectional"))
    )
    (net (code "50") (name "unconnected-(IC2-LBO-Pad17)") (class "Default")
      (node (ref "IC2") (pin "17") (pinfunction "LBO_17") (pintype "bidirectional"))
    )
    (net (code "51") (name "unconnected-(IC3-BYPASS-Pad4)") (class "Default")
      (node (ref "IC3") (pin "4") (pinfunction "BYPASS_4") (pintype "bidirectional"))
    )
    (net (code "52") (name "unconnected-(S2-Pad1)") (class "Default")
      (node (ref "S2") (pin "1") (pinfunction "1_1") (pintype "passive"))
    )
    (net (code "53") (name "unconnected-(U3-RH1_NH3-PadC)") (class "Default")
      (node (ref "U3") (pin "C") (pinfunction "RH1_NH3_C") (pintype "passive"))
    )
    (net (code "54") (name "unconnected-(U3-RH2_NH3-PadE)") (class "Default")
      (node (ref "U3") (pin "E") (pinfunction "RH2_NH3_E") (pintype "passive"))
    )
    (net (code "55") (name "unconnected-(U3-RS1_NH3-PadD)") (class "Default")
      (node (ref "U3") (pin "D") (pinfunction "RS1_NH3_D") (pintype "passive"))
    )
    (net (code "56") (name "unconnected-(U3-RS2_NH3-PadF)") (class "Default")
      (node (ref "U3") (pin "F") (pinfunction "RS2_NH3_F") (pintype "passive"))
    )
    (net (code "57") (name "unconnected-(U5-P0.00{slash}XL1-Pad13)") (class "Default")
      (node (ref "U5") (pin "13") (pinfunction "P0.00/XL1_13") (pintype "bidirectional"))
    )
    (net (code "58") (name "unconnected-(U5-P0.01{slash}XL2-Pad14)") (class "Default")
      (node (ref "U5") (pin "14") (pinfunction "P0.01/XL2_14") (pintype "bidirectional"))
    )
    (net (code "59") (name "unconnected-(U5-P0.02{slash}AIN0-Pad15)") (class "Default")
      (node (ref "U5") (pin "15") (pinfunction "P0.02/AIN0_15") (pintype "bidirectional"))
    )
    (net (code "60") (name "unconnected-(U5-P0.04{slash}AIN2-Pad17)") (class "Default")
      (node (ref "U5") (pin "17") (pinfunction "P0.04/AIN2_17") (pintype "bidirectional"))
    )
    (net (code "61") (name "unconnected-(U5-P0.06-Pad19)") (class "Default")
      (node (ref "U5") (pin "19") (pinfunction "P0.06_19") (pintype "bidirectional"))
    )
    (net (code "62") (name "unconnected-(U5-P0.07-Pad20)") (class "Default")
      (node (ref "U5") (pin "20") (pinfunction "P0.07_20") (pintype "bidirectional"))
    )
    (net (code "63") (name "unconnected-(U5-P0.08-Pad21)") (class "Default")
      (node (ref "U5") (pin "21") (pinfunction "P0.08_21") (pintype "bidirectional"))
    )
    (net (code "64") (name "unconnected-(U5-P0.09{slash}NFC1-Pad22)") (class "Default")
      (node (ref "U5") (pin "22") (pinfunction "P0.09/NFC1_22") (pintype "bidirectional"))
    )
    (net (code "65") (name "unconnected-(U5-P0.10{slash}NFC2-Pad23)") (class "Default")
      (node (ref "U5") (pin "23") (pinfunction "P0.10/NFC2_23") (pintype "bidirectional"))
    )
    (net (code "66") (name "unconnected-(U5-P0.11-Pad25)") (class "Default")
      (node (ref "U5") (pin "25") (pinfunction "P0.11_25") (pintype "bidirectional"))
    )
    (net (code "67") (name "unconnected-(U5-P0.12-Pad26)") (class "Default")
      (node (ref "U5") (pin "26") (pinfunction "P0.12_26") (pintype "bidirectional"))
    )
    (net (code "68") (name "unconnected-(U5-P0.13-Pad27)") (class "Default")
      (node (ref "U5") (pin "27") (pinfunction "P0.13_27") (pintype "bidirectional"))
    )
    (net (code "69") (name "unconnected-(U5-P0.14{slash}TRACEDATA(3)-Pad28)") (class "Default")
      (node (ref "U5") (pin "28") (pinfunction "P0.14/TRACEDATA(3)_28") (pintype "bidirectional"))
    )
    (net (code "70") (name "unconnected-(U5-P0.15{slash}TRACEDATA(2)-Pad29)") (class "Default")
      (node (ref "U5") (pin "29") (pinfunction "P0.15/TRACEDATA(2)_29") (pintype "bidirectional"))
    )
    (net (code "71") (name "unconnected-(U5-P0.16{slash}TRACEDATA(1)-Pad30)") (class "Default")
      (node (ref "U5") (pin "30") (pinfunction "P0.16/TRACEDATA(1)_30") (pintype "bidirectional"))
    )
    (net (code "72") (name "unconnected-(U5-P0.17-Pad31)") (class "Default")
      (node (ref "U5") (pin "31") (pinfunction "P0.17_31") (pintype "bidirectional"))
    )
    (net (code "73") (name "unconnected-(U5-P0.18{slash}TRACEDATA(0)-Pad32)") (class "Default")
      (node (ref "U5") (pin "32") (pinfunction "P0.18/TRACEDATA(0)_32") (pintype "bidirectional"))
    )
    (net (code "74") (name "unconnected-(U5-P0.19-Pad33)") (class "Default")
      (node (ref "U5") (pin "33") (pinfunction "P0.19_33") (pintype "bidirectional"))
    )
    (net (code "75") (name "unconnected-(U5-P0.20{slash}TRACECLK-Pad34)") (class "Default")
      (node (ref "U5") (pin "34") (pinfunction "P0.20/TRACECLK_34") (pintype "bidirectional"))
    )
    (net (code "76") (name "unconnected-(U5-P0.21{slash}RESET-Pad35)") (class "Default")
      (node (ref "U5") (pin "35") (pinfunction "P0.21/RESET_35") (pintype "bidirectional"))
    )
    (net (code "77") (name "unconnected-(U5-P0.22-Pad38)") (class "Default")
      (node (ref "U5") (pin "38") (pinfunction "P0.22_38") (pintype "bidirectional"))
    )
    (net (code "78") (name "unconnected-(U5-P0.23-Pad41)") (class "Default")
      (node (ref "U5") (pin "41") (pinfunction "P0.23_41") (pintype "bidirectional"))
    )
    (net (code "79") (name "unconnected-(U5-P0.24-Pad40)") (class "Default")
      (node (ref "U5") (pin "40") (pinfunction "P0.24_40") (pintype "bidirectional"))
    )
    (net (code "80") (name "unconnected-(U5-P0.28{slash}AIN4-Pad5)") (class "Default")
      (node (ref "U5") (pin "5") (pinfunction "P0.28/AIN4_5") (pintype "bidirectional"))
    )
    (net (code "81") (name "unconnected-(U5-P0.29{slash}AIN5-Pad6)") (class "Default")
      (node (ref "U5") (pin "6") (pinfunction "P0.29/AIN5_6") (pintype "bidirectional"))
    )
    (net (code "82") (name "unconnected-(U5-P0.30AIN6-Pad7)") (class "Default")
      (node (ref "U5") (pin "7") (pinfunction "P0.30AIN6_7") (pintype "bidirectional"))
    )
    (net (code "83") (name "unconnected-(U5-P0.31{slash}AIN7-Pad8)") (class "Default")
      (node (ref "U5") (pin "8") (pinfunction "P0.31/AIN7_8") (pintype "bidirectional"))
    )
    (net (code "84") (name "unconnected-(U5-SWDCLK-Pad36)") (class "Default")
      (node (ref "U5") (pin "36") (pinfunction "SWDCLK_36") (pintype "input"))
    )
    (net (code "85") (name "unconnected-(U5-SWDIO-Pad37)") (class "Default")
      (node (ref "U5") (pin "37") (pinfunction "SWDIO_37") (pintype "bidirectional"))
    )
    (net (code "86") (name "unconnected-(U7-ADC1-Pad16)") (class "Default")
      (node (ref "U7") (pin "16") (pinfunction "ADC1_16") (pintype "input"))
    )
    (net (code "87") (name "unconnected-(U7-ADC2-Pad15)") (class "Default")
      (node (ref "U7") (pin "15") (pinfunction "ADC2_15") (pintype "input"))
    )
    (net (code "88") (name "unconnected-(U7-ADC3-Pad13)") (class "Default")
      (node (ref "U7") (pin "13") (pinfunction "ADC3_13") (pintype "input"))
    )
    (net (code "89") (name "unconnected-(U7-INT1-Pad11)") (class "Default")
      (node (ref "U7") (pin "11") (pinfunction "INT1_11") (pintype "input"))
    )
    (net (code "90") (name "unconnected-(U7-INT2-Pad9)") (class "Default")
      (node (ref "U7") (pin "9") (pinfunction "INT2_9") (pintype "input"))
    )
  )
)
